# New_Pendant_wiring.net
KiCad netlist of a schematic drawn in EAGLE
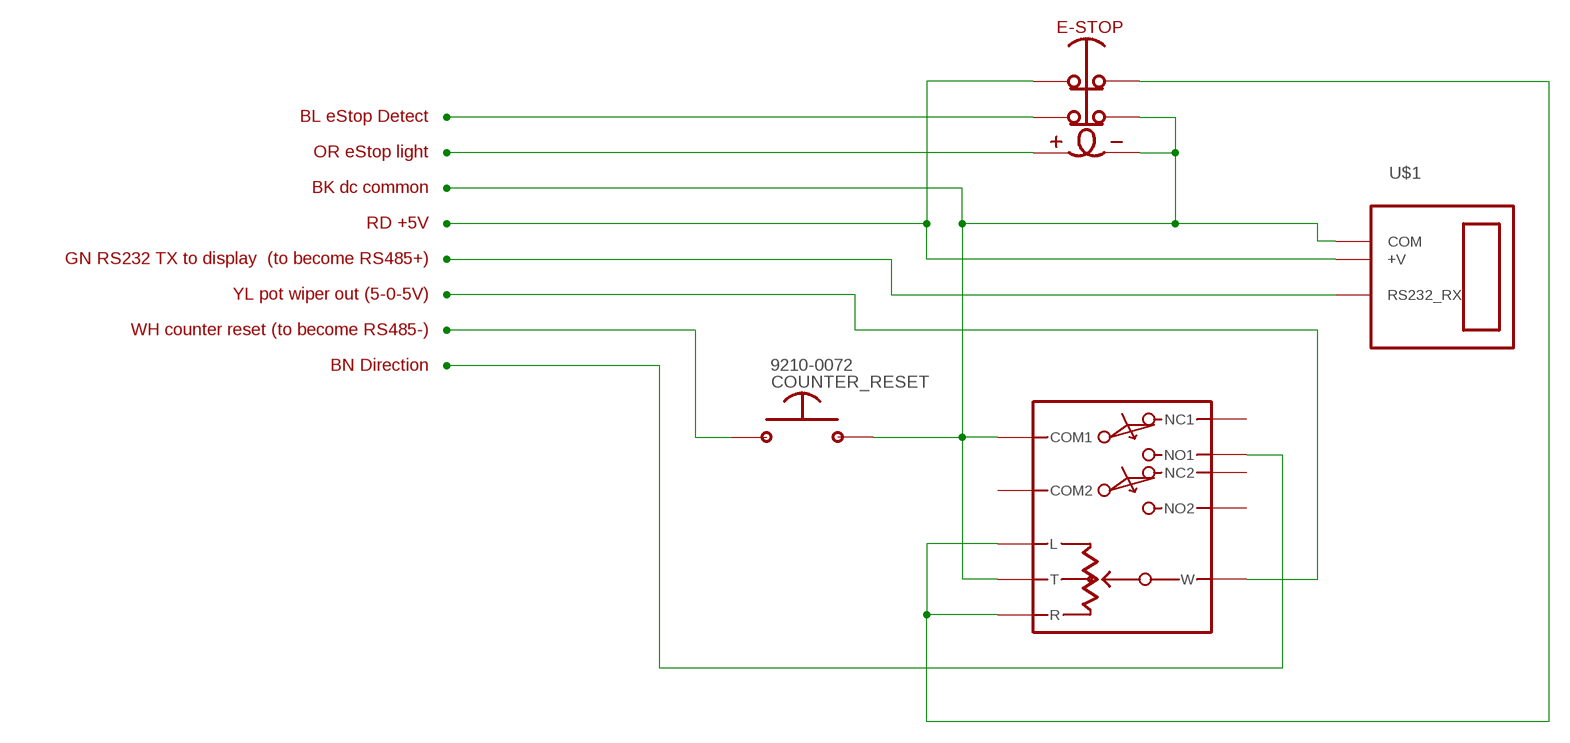
[diagram p0: schematic, sheet 1]

(export (version "E")
  (design (tool "Eeschema 10.0.6"))
  (components
    (comp (ref "COUNTER_RESET")
      (value "SWITCH_MOM_NO")
      (footprint "eagle-import:BOGUS")
      (libsource (lib "eagle-import") (part "SWITCH_MOM_NO"))
    )
    (comp (ref "U$1")
      (value "DISPLAY_COUNTER_ELW_SERIAL")
      (footprint "eagle-import:BOGUS")
      (libsource (lib "eagle-import") (part "DISPLAY_COUNTER_ELW_SERIAL"))
    )
    (comp (ref "U$2")
      (value "SWITCH_ESTOP_LIGHTED")
      (footprint "eagle-import:BOGUS")
      (libsource (lib "eagle-import") (part "SWITCH_ESTOP_LIGHTED"))
    )
    (comp (ref "U$3")
      (value "JOYSTICK_PRO-5")
      (footprint "eagle-import:BOGUS")
      (libsource (lib "eagle-import") (part "JOYSTICK_PRO-5"))
    )
  )
  (nets
    (net (code "1") (name "Net-(U$1-+V)") (class "Default")
      (node (ref "U$1") (pin "P$1") (pinfunction "+V_P$1") (pintype "bidirectional"))
      (node (ref "U$2") (pin "P$1") (pinfunction "P$1_P$1") (pintype "bidirectional"))
    )
    (net (code "2") (name "Net-(U$1-COM)") (class "Default")
      (node (ref "COUNTER_RESET") (pin "P$2") (pinfunction "P$2_P$2") (pintype "bidirectional"))
      (node (ref "U$1") (pin "P$2") (pinfunction "COM_P$2") (pintype "bidirectional"))
      (node (ref "U$2") (pin "P$4") (pinfunction "P$4_P$4") (pintype "bidirectional"))
      (node (ref "U$2") (pin "P$6") (pinfunction "P$6_P$6") (pintype "bidirectional"))
      (node (ref "U$3") (pin "P$1") (pinfunction "COM1_P$1") (pintype "bidirectional"))
      (node (ref "U$3") (pin "P$9") (pinfunction "T_P$9") (pintype "bidirectional"))
    )
    (net (code "3") (name "Net-(U$3-L)") (class "Default")
      (node (ref "U$2") (pin "P$3") (pinfunction "P$3_P$3") (pintype "bidirectional"))
      (node (ref "U$3") (pin "P$3") (pinfunction "L_P$3") (pintype "bidirectional"))
      (node (ref "U$3") (pin "P$8") (pinfunction "R_P$8") (pintype "bidirectional"))
    )
    (net (code "4") (name "unconnected-(COUNTER_RESET-PadP$1)") (class "Default")
      (node (ref "COUNTER_RESET") (pin "P$1") (pinfunction "P$1_P$1") (pintype "bidirectional"))
    )
    (net (code "5") (name "unconnected-(U$1-RS232_RX-PadP$3)") (class "Default")
      (node (ref "U$1") (pin "P$3") (pinfunction "RS232_RX_P$3") (pintype "bidirectional"))
    )
    (net (code "6") (name "unconnected-(U$2-PadP$2)") (class "Default")
      (node (ref "U$2") (pin "P$2") (pinfunction "P$2_P$2") (pintype "bidirectional"))
    )
    (net (code "7") (name "unconnected-(U$2-PadP$5)") (class "Default")
      (node (ref "U$2") (pin "P$5") (pinfunction "P$5_P$5") (pintype "bidirectional"))
    )
    (net (code "8") (name "unconnected-(U$3-COM2-PadP$2)") (class "Default")
      (node (ref "U$3") (pin "P$2") (pinfunction "COM2_P$2") (pintype "bidirectional"))
    )
    (net (code "9") (name "unconnected-(U$3-NC1-PadP$4)") (class "Default")
      (node (ref "U$3") (pin "P$4") (pinfunction "NC1_P$4") (pintype "bidirectional"))
    )
    (net (code "10") (name "unconnected-(U$3-NC2-PadP$5)") (class "Default")
      (node (ref "U$3") (pin "P$5") (pinfunction "NC2_P$5") (pintype "bidirectional"))
    )
    (net (code "11") (name "unconnected-(U$3-NO1-PadP$6)") (class "Default")
      (node (ref "U$3") (pin "P$6") (pinfunction "NO1_P$6") (pintype "bidirectional"))
    )
    (net (code "12") (name "unconnected-(U$3-NO2-PadP$7)") (class "Default")
      (node (ref "U$3") (pin "P$7") (pinfunction "NO2_P$7") (pintype "bidirectional"))
    )
    (net (code "13") (name "unconnected-(U$3-W-PadP$10)") (class "Default")
      (node (ref "U$3") (pin "P$10") (pinfunction "W_P$10") (pintype "bidirectional"))
    )
  )
)
